# B142A.net
KiCad netlist of a schematic drawn in EAGLE
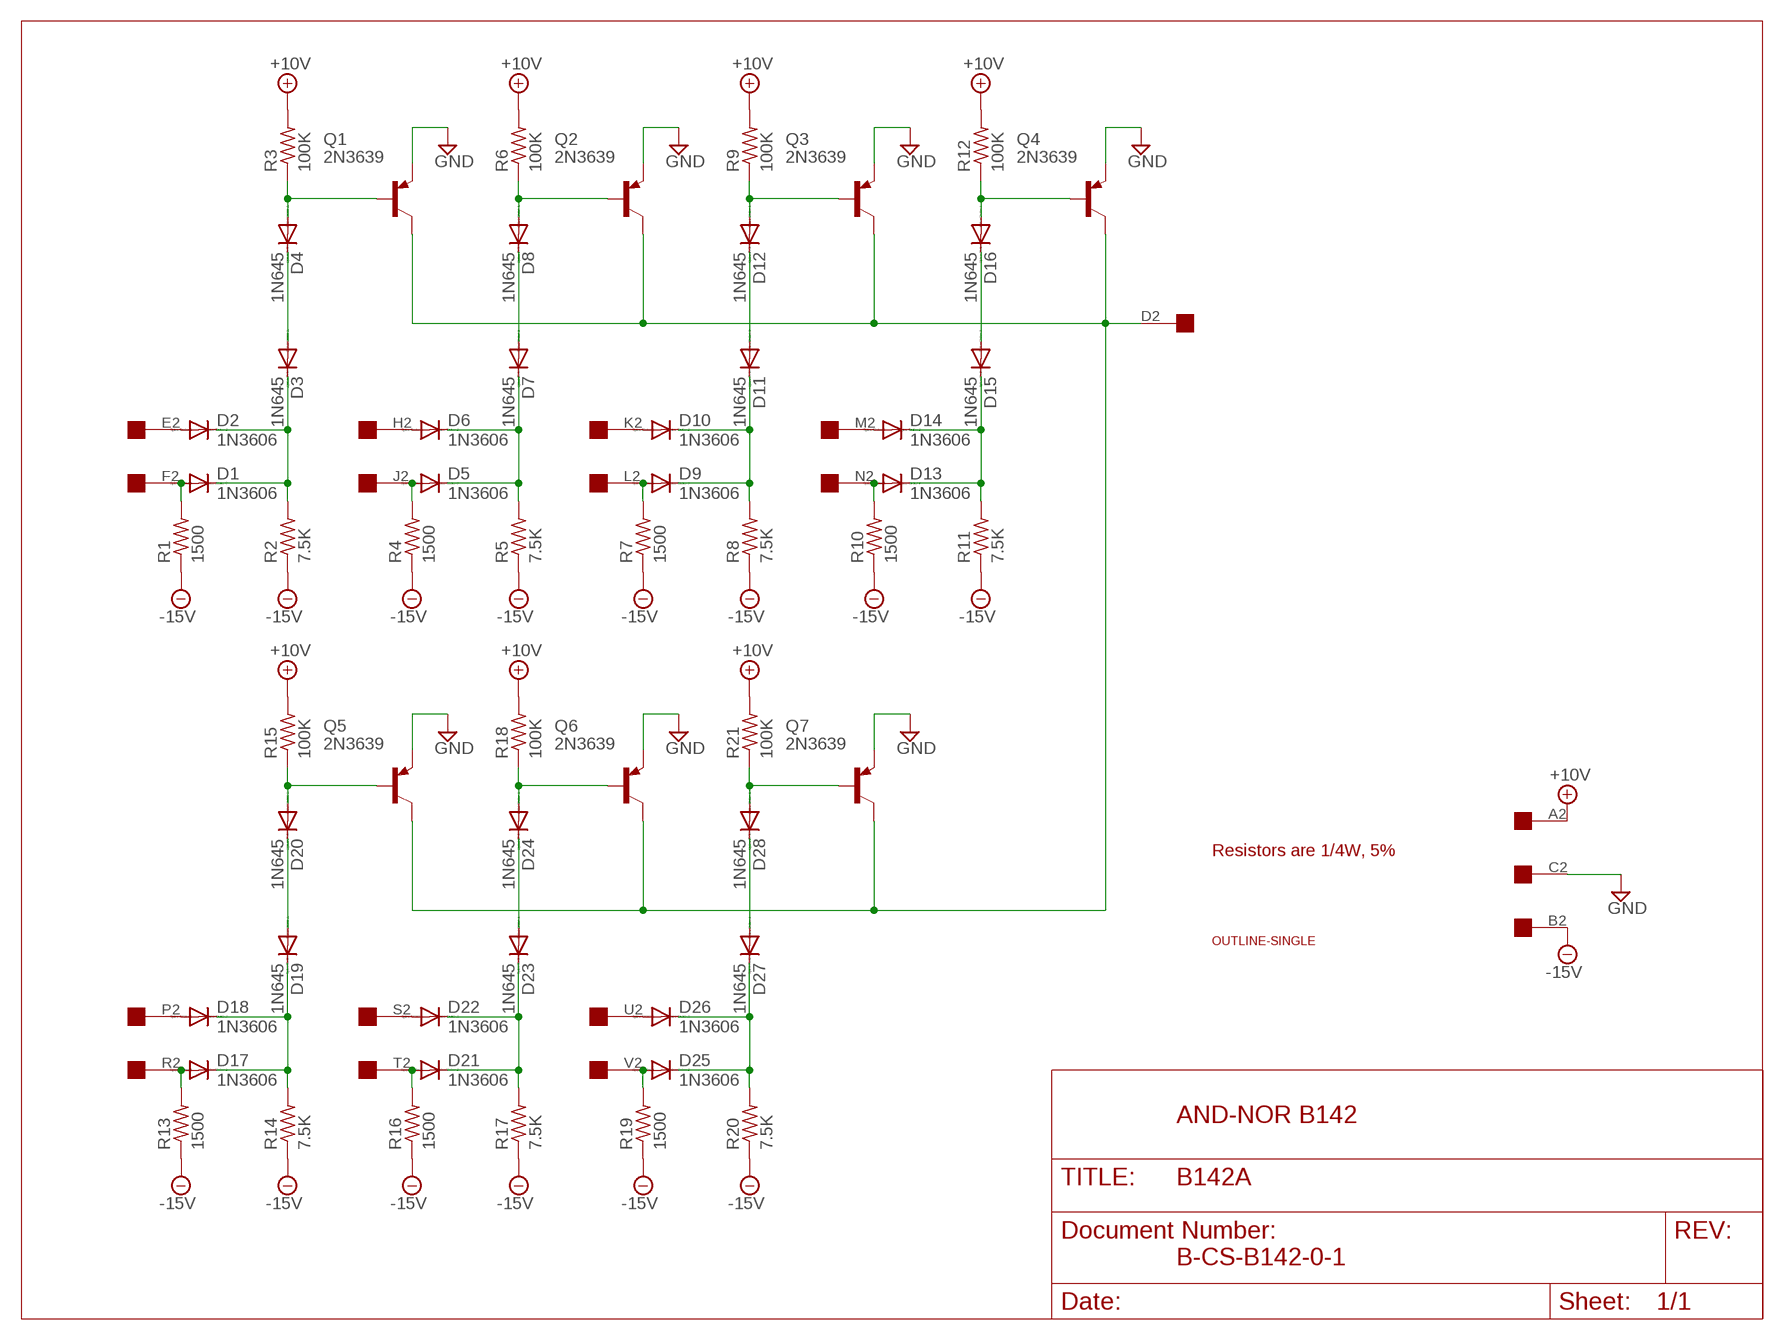
[diagram p0: schematic, sheet 1]

(export (version "E")
  (design (tool "Eeschema 10.0.6"))
  (components
    (comp (ref "D1")
      (value "1N3606")
      (footprint "eagle-import:DO35-10")
      (libsource (lib "eagle-import") (part "1N4148DO35-10"))
    )
    (comp (ref "D2")
      (value "1N3606")
      (footprint "eagle-import:DO35-10")
      (libsource (lib "eagle-import") (part "1N4148DO35-10"))
    )
    (comp (ref "D3")
      (value "1N645")
      (footprint "eagle-import:DO35-10")
      (libsource (lib "eagle-import") (part "1N4148DO35-10"))
    )
    (comp (ref "D4")
      (value "1N645")
      (footprint "eagle-import:DO35-10")
      (libsource (lib "eagle-import") (part "1N4148DO35-10"))
    )
    (comp (ref "D5")
      (value "1N3606")
      (footprint "eagle-import:DO35-10")
      (libsource (lib "eagle-import") (part "1N4148DO35-10"))
    )
    (comp (ref "D6")
      (value "1N3606")
      (footprint "eagle-import:DO35-10")
      (libsource (lib "eagle-import") (part "1N4148DO35-10"))
    )
    (comp (ref "D7")
      (value "1N645")
      (footprint "eagle-import:DO35-10")
      (libsource (lib "eagle-import") (part "1N4148DO35-10"))
    )
    (comp (ref "D8")
      (value "1N645")
      (footprint "eagle-import:DO35-10")
      (libsource (lib "eagle-import") (part "1N4148DO35-10"))
    )
    (comp (ref "D9")
      (value "1N3606")
      (footprint "eagle-import:DO35-10")
      (libsource (lib "eagle-import") (part "1N4148DO35-10"))
    )
    (comp (ref "D10")
      (value "1N3606")
      (footprint "eagle-import:DO35-10")
      (libsource (lib "eagle-import") (part "1N4148DO35-10"))
    )
    (comp (ref "D11")
      (value "1N645")
      (footprint "eagle-import:DO35-10")
      (libsource (lib "eagle-import") (part "1N4148DO35-10"))
    )
    (comp (ref "D12")
      (value "1N645")
      (footprint "eagle-import:DO35-10")
      (libsource (lib "eagle-import") (part "1N4148DO35-10"))
    )
    (comp (ref "D13")
      (value "1N3606")
      (footprint "eagle-import:DO35-10")
      (libsource (lib "eagle-import") (part "1N4148DO35-10"))
    )
    (comp (ref "D14")
      (value "1N3606")
      (footprint "eagle-import:DO35-10")
      (libsource (lib "eagle-import") (part "1N4148DO35-10"))
    )
    (comp (ref "D15")
      (value "1N645")
      (footprint "eagle-import:DO35-10")
      (libsource (lib "eagle-import") (part "1N4148DO35-10"))
    )
    (comp (ref "D16")
      (value "1N645")
      (footprint "eagle-import:DO35-10")
      (libsource (lib "eagle-import") (part "1N4148DO35-10"))
    )
    (comp (ref "D17")
      (value "1N3606")
      (footprint "eagle-import:DO35-10")
      (libsource (lib "eagle-import") (part "1N4148DO35-10"))
    )
    (comp (ref "D18")
      (value "1N3606")
      (footprint "eagle-import:DO35-10")
      (libsource (lib "eagle-import") (part "1N4148DO35-10"))
    )
    (comp (ref "D19")
      (value "1N645")
      (footprint "eagle-import:DO35-10")
      (libsource (lib "eagle-import") (part "1N4148DO35-10"))
    )
    (comp (ref "D20")
      (value "1N645")
      (footprint "eagle-import:DO35-10")
      (libsource (lib "eagle-import") (part "1N4148DO35-10"))
    )
    (comp (ref "D21")
      (value "1N3606")
      (footprint "eagle-import:DO35-10")
      (libsource (lib "eagle-import") (part "1N4148DO35-10"))
    )
    (comp (ref "D22")
      (value "1N3606")
      (footprint "eagle-import:DO35-10")
      (libsource (lib "eagle-import") (part "1N4148DO35-10"))
    )
    (comp (ref "D23")
      (value "1N645")
      (footprint "eagle-import:DO35-10")
      (libsource (lib "eagle-import") (part "1N4148DO35-10"))
    )
    (comp (ref "D24")
      (value "1N645")
      (footprint "eagle-import:DO35-10")
      (libsource (lib "eagle-import") (part "1N4148DO35-10"))
    )
    (comp (ref "D25")
      (value "1N3606")
      (footprint "eagle-import:DO35-10")
      (libsource (lib "eagle-import") (part "1N4148DO35-10"))
    )
    (comp (ref "D26")
      (value "1N3606")
      (footprint "eagle-import:DO35-10")
      (libsource (lib "eagle-import") (part "1N4148DO35-10"))
    )
    (comp (ref "D27")
      (value "1N645")
      (footprint "eagle-import:DO35-10")
      (libsource (lib "eagle-import") (part "1N4148DO35-10"))
    )
    (comp (ref "D28")
      (value "1N645")
      (footprint "eagle-import:DO35-10")
      (libsource (lib "eagle-import") (part "1N4148DO35-10"))
    )
    (comp (ref "Q1")
      (value "2N3639")
      (footprint "eagle-import:TO39")
      (libsource (lib "eagle-import") (part "2N3637"))
    )
    (comp (ref "Q2")
      (value "2N3639")
      (footprint "eagle-import:TO39")
      (libsource (lib "eagle-import") (part "2N3637"))
    )
    (comp (ref "Q3")
      (value "2N3639")
      (footprint "eagle-import:TO39")
      (libsource (lib "eagle-import") (part "2N3637"))
    )
    (comp (ref "Q4")
      (value "2N3639")
      (footprint "eagle-import:TO39")
      (libsource (lib "eagle-import") (part "2N3637"))
    )
    (comp (ref "Q5")
      (value "2N3639")
      (footprint "eagle-import:TO39")
      (libsource (lib "eagle-import") (part "2N3637"))
    )
    (comp (ref "Q6")
      (value "2N3639")
      (footprint "eagle-import:TO39")
      (libsource (lib "eagle-import") (part "2N3637"))
    )
    (comp (ref "Q7")
      (value "2N3639")
      (footprint "eagle-import:TO39")
      (libsource (lib "eagle-import") (part "2N3637"))
    )
    (comp (ref "R1")
      (value "1500")
      (footprint "eagle-import:0207_10")
      (libsource (lib "eagle-import") (part "R-US_0207/10"))
    )
    (comp (ref "R2")
      (value "7.5K")
      (footprint "eagle-import:0207_10")
      (libsource (lib "eagle-import") (part "R-US_0207/10"))
    )
    (comp (ref "R3")
      (value "100K")
      (footprint "eagle-import:0207_10")
      (libsource (lib "eagle-import") (part "R-US_0207/10"))
    )
    (comp (ref "R4")
      (value "1500")
      (footprint "eagle-import:0207_10")
      (libsource (lib "eagle-import") (part "R-US_0207/10"))
    )
    (comp (ref "R5")
      (value "7.5K")
      (footprint "eagle-import:0207_10")
      (libsource (lib "eagle-import") (part "R-US_0207/10"))
    )
    (comp (ref "R6")
      (value "100K")
      (footprint "eagle-import:0207_10")
      (libsource (lib "eagle-import") (part "R-US_0207/10"))
    )
    (comp (ref "R7")
      (value "1500")
      (footprint "eagle-import:0207_10")
      (libsource (lib "eagle-import") (part "R-US_0207/10"))
    )
    (comp (ref "R8")
      (value "7.5K")
      (footprint "eagle-import:0207_10")
      (libsource (lib "eagle-import") (part "R-US_0207/10"))
    )
    (comp (ref "R9")
      (value "100K")
      (footprint "eagle-import:0207_10")
      (libsource (lib "eagle-import") (part "R-US_0207/10"))
    )
    (comp (ref "R10")
      (value "1500")
      (footprint "eagle-import:0207_10")
      (libsource (lib "eagle-import") (part "R-US_0207/10"))
    )
    (comp (ref "R11")
      (value "7.5K")
      (footprint "eagle-import:0207_10")
      (libsource (lib "eagle-import") (part "R-US_0207/10"))
    )
    (comp (ref "R12")
      (value "100K")
      (footprint "eagle-import:0207_10")
      (libsource (lib "eagle-import") (part "R-US_0207/10"))
    )
    (comp (ref "R13")
      (value "1500")
      (footprint "eagle-import:0207_10")
      (libsource (lib "eagle-import") (part "R-US_0207/10"))
    )
    (comp (ref "R14")
      (value "7.5K")
      (footprint "eagle-import:0207_10")
      (libsource (lib "eagle-import") (part "R-US_0207/10"))
    )
    (comp (ref "R15")
      (value "100K")
      (footprint "eagle-import:0207_10")
      (libsource (lib "eagle-import") (part "R-US_0207/10"))
    )
    (comp (ref "R16")
      (value "1500")
      (footprint "eagle-import:0207_10")
      (libsource (lib "eagle-import") (part "R-US_0207/10"))
    )
    (comp (ref "R17")
      (value "7.5K")
      (footprint "eagle-import:0207_10")
      (libsource (lib "eagle-import") (part "R-US_0207/10"))
    )
    (comp (ref "R18")
      (value "100K")
      (footprint "eagle-import:0207_10")
      (libsource (lib "eagle-import") (part "R-US_0207/10"))
    )
    (comp (ref "R19")
      (value "1500")
      (footprint "eagle-import:0207_10")
      (libsource (lib "eagle-import") (part "R-US_0207/10"))
    )
    (comp (ref "R20")
      (value "7.5K")
      (footprint "eagle-import:0207_10")
      (libsource (lib "eagle-import") (part "R-US_0207/10"))
    )
    (comp (ref "R21")
      (value "100K")
      (footprint "eagle-import:0207_10")
      (libsource (lib "eagle-import") (part "R-US_0207/10"))
    )
    (comp (ref "U$1")
      (value "OUTLINE-SINGLE")
      (footprint "eagle-import:SINGLE")
      (libsource (lib "eagle-import") (part "OUTLINE-SINGLE"))
    )
    (comp (ref "U$2")
      (value "EDGE-1")
      (footprint "eagle-import:EDGE-CON1")
      (libsource (lib "eagle-import") (part "EDGE-1"))
    )
  )
  (nets
    (net (code "1") (name "+10V") (class "Default")
      (node (ref "R12") (pin "2") (pinfunction "2_2") (pintype "passive"))
      (node (ref "R15") (pin "2") (pinfunction "2_2") (pintype "passive"))
      (node (ref "R18") (pin "2") (pinfunction "2_2") (pintype "passive"))
      (node (ref "R21") (pin "2") (pinfunction "2_2") (pintype "passive"))
      (node (ref "R3") (pin "2") (pinfunction "2_2") (pintype "passive"))
      (node (ref "R6") (pin "2") (pinfunction "2_2") (pintype "passive"))
      (node (ref "R9") (pin "2") (pinfunction "2_2") (pintype "passive"))
      (node (ref "U$2") (pin "A2") (pinfunction "1_A2") (pintype "bidirectional"))
    )
    (net (code "2") (name "-15V") (class "Default")
      (node (ref "R1") (pin "1") (pinfunction "1_1") (pintype "passive"))
      (node (ref "R10") (pin "1") (pinfunction "1_1") (pintype "passive"))
      (node (ref "R11") (pin "1") (pinfunction "1_1") (pintype "passive"))
      (node (ref "R13") (pin "1") (pinfunction "1_1") (pintype "passive"))
      (node (ref "R14") (pin "1") (pinfunction "1_1") (pintype "passive"))
      (node (ref "R16") (pin "1") (pinfunction "1_1") (pintype "passive"))
      (node (ref "R17") (pin "1") (pinfunction "1_1") (pintype "passive"))
      (node (ref "R19") (pin "1") (pinfunction "1_1") (pintype "passive"))
      (node (ref "R2") (pin "1") (pinfunction "1_1") (pintype "passive"))
      (node (ref "R20") (pin "1") (pinfunction "1_1") (pintype "passive"))
      (node (ref "R4") (pin "1") (pinfunction "1_1") (pintype "passive"))
      (node (ref "R5") (pin "1") (pinfunction "1_1") (pintype "passive"))
      (node (ref "R7") (pin "1") (pinfunction "1_1") (pintype "passive"))
      (node (ref "R8") (pin "1") (pinfunction "1_1") (pintype "passive"))
      (node (ref "U$2") (pin "B2") (pinfunction "1_B2") (pintype "bidirectional"))
    )
    (net (code "3") (name "GND") (class "Default")
      (node (ref "Q1") (pin "1") (pinfunction "E_1") (pintype "passive"))
      (node (ref "Q2") (pin "1") (pinfunction "E_1") (pintype "passive"))
      (node (ref "Q3") (pin "1") (pinfunction "E_1") (pintype "passive"))
      (node (ref "Q4") (pin "1") (pinfunction "E_1") (pintype "passive"))
      (node (ref "Q5") (pin "1") (pinfunction "E_1") (pintype "passive"))
      (node (ref "Q6") (pin "1") (pinfunction "E_1") (pintype "passive"))
      (node (ref "Q7") (pin "1") (pinfunction "E_1") (pintype "passive"))
      (node (ref "U$2") (pin "C2") (pinfunction "1_C2") (pintype "bidirectional"))
    )
    (net (code "4") (name "Net-(D1-PadC)") (class "Default")
      (node (ref "D1") (pin "C") (pinfunction "C_C") (pintype "passive"))
      (node (ref "D2") (pin "C") (pinfunction "C_C") (pintype "passive"))
      (node (ref "D3") (pin "C") (pinfunction "C_C") (pintype "passive"))
      (node (ref "R2") (pin "2") (pinfunction "2_2") (pintype "passive"))
    )
    (net (code "5") (name "Net-(D3-PadA)") (class "Default")
      (node (ref "D3") (pin "A") (pinfunction "A_A") (pintype "passive"))
      (node (ref "D4") (pin "C") (pinfunction "C_C") (pintype "passive"))
    )
    (net (code "6") (name "Net-(D5-PadC)") (class "Default")
      (node (ref "D5") (pin "C") (pinfunction "C_C") (pintype "passive"))
      (node (ref "D6") (pin "C") (pinfunction "C_C") (pintype "passive"))
      (node (ref "D7") (pin "C") (pinfunction "C_C") (pintype "passive"))
      (node (ref "R5") (pin "2") (pinfunction "2_2") (pintype "passive"))
    )
    (net (code "7") (name "Net-(D7-PadA)") (class "Default")
      (node (ref "D7") (pin "A") (pinfunction "A_A") (pintype "passive"))
      (node (ref "D8") (pin "C") (pinfunction "C_C") (pintype "passive"))
    )
    (net (code "8") (name "Net-(D10-PadC)") (class "Default")
      (node (ref "D10") (pin "C") (pinfunction "C_C") (pintype "passive"))
      (node (ref "D11") (pin "C") (pinfunction "C_C") (pintype "passive"))
      (node (ref "D9") (pin "C") (pinfunction "C_C") (pintype "passive"))
      (node (ref "R8") (pin "2") (pinfunction "2_2") (pintype "passive"))
    )
    (net (code "9") (name "Net-(D11-PadA)") (class "Default")
      (node (ref "D11") (pin "A") (pinfunction "A_A") (pintype "passive"))
      (node (ref "D12") (pin "C") (pinfunction "C_C") (pintype "passive"))
    )
    (net (code "10") (name "Net-(D13-PadC)") (class "Default")
      (node (ref "D13") (pin "C") (pinfunction "C_C") (pintype "passive"))
      (node (ref "D14") (pin "C") (pinfunction "C_C") (pintype "passive"))
      (node (ref "D15") (pin "C") (pinfunction "C_C") (pintype "passive"))
      (node (ref "R11") (pin "2") (pinfunction "2_2") (pintype "passive"))
    )
    (net (code "11") (name "Net-(D15-PadA)") (class "Default")
      (node (ref "D15") (pin "A") (pinfunction "A_A") (pintype "passive"))
      (node (ref "D16") (pin "C") (pinfunction "C_C") (pintype "passive"))
    )
    (net (code "12") (name "Net-(D17-PadC)") (class "Default")
      (node (ref "D17") (pin "C") (pinfunction "C_C") (pintype "passive"))
      (node (ref "D18") (pin "C") (pinfunction "C_C") (pintype "passive"))
      (node (ref "D19") (pin "C") (pinfunction "C_C") (pintype "passive"))
      (node (ref "R14") (pin "2") (pinfunction "2_2") (pintype "passive"))
    )
    (net (code "13") (name "Net-(D19-PadA)") (class "Default")
      (node (ref "D19") (pin "A") (pinfunction "A_A") (pintype "passive"))
      (node (ref "D20") (pin "C") (pinfunction "C_C") (pintype "passive"))
    )
    (net (code "14") (name "Net-(D21-PadC)") (class "Default")
      (node (ref "D21") (pin "C") (pinfunction "C_C") (pintype "passive"))
      (node (ref "D22") (pin "C") (pinfunction "C_C") (pintype "passive"))
      (node (ref "D23") (pin "C") (pinfunction "C_C") (pintype "passive"))
      (node (ref "R17") (pin "2") (pinfunction "2_2") (pintype "passive"))
    )
    (net (code "15") (name "Net-(D23-PadA)") (class "Default")
      (node (ref "D23") (pin "A") (pinfunction "A_A") (pintype "passive"))
      (node (ref "D24") (pin "C") (pinfunction "C_C") (pintype "passive"))
    )
    (net (code "16") (name "Net-(D25-PadC)") (class "Default")
      (node (ref "D25") (pin "C") (pinfunction "C_C") (pintype "passive"))
      (node (ref "D26") (pin "C") (pinfunction "C_C") (pintype "passive"))
      (node (ref "D27") (pin "C") (pinfunction "C_C") (pintype "passive"))
      (node (ref "R20") (pin "2") (pinfunction "2_2") (pintype "passive"))
    )
    (net (code "17") (name "Net-(D27-PadA)") (class "Default")
      (node (ref "D27") (pin "A") (pinfunction "A_A") (pintype "passive"))
      (node (ref "D28") (pin "C") (pinfunction "C_C") (pintype "passive"))
    )
    (net (code "18") (name "Net-(Q1-B)") (class "Default")
      (node (ref "D4") (pin "A") (pinfunction "A_A") (pintype "passive"))
      (node (ref "Q1") (pin "2") (pinfunction "B_2") (pintype "passive"))
      (node (ref "R3") (pin "1") (pinfunction "1_1") (pintype "passive"))
    )
    (net (code "19") (name "Net-(Q1-C)") (class "Default")
      (node (ref "Q1") (pin "3") (pinfunction "C_3") (pintype "passive"))
      (node (ref "Q2") (pin "3") (pinfunction "C_3") (pintype "passive"))
      (node (ref "Q3") (pin "3") (pinfunction "C_3") (pintype "passive"))
      (node (ref "Q4") (pin "3") (pinfunction "C_3") (pintype "passive"))
      (node (ref "Q5") (pin "3") (pinfunction "C_3") (pintype "passive"))
      (node (ref "Q6") (pin "3") (pinfunction "C_3") (pintype "passive"))
      (node (ref "Q7") (pin "3") (pinfunction "C_3") (pintype "passive"))
      (node (ref "U$2") (pin "D2") (pinfunction "1_D2") (pintype "bidirectional"))
    )
    (net (code "20") (name "Net-(Q2-B)") (class "Default")
      (node (ref "D8") (pin "A") (pinfunction "A_A") (pintype "passive"))
      (node (ref "Q2") (pin "2") (pinfunction "B_2") (pintype "passive"))
      (node (ref "R6") (pin "1") (pinfunction "1_1") (pintype "passive"))
    )
    (net (code "21") (name "Net-(Q3-B)") (class "Default")
      (node (ref "D12") (pin "A") (pinfunction "A_A") (pintype "passive"))
      (node (ref "Q3") (pin "2") (pinfunction "B_2") (pintype "passive"))
      (node (ref "R9") (pin "1") (pinfunction "1_1") (pintype "passive"))
    )
    (net (code "22") (name "Net-(Q4-B)") (class "Default")
      (node (ref "D16") (pin "A") (pinfunction "A_A") (pintype "passive"))
      (node (ref "Q4") (pin "2") (pinfunction "B_2") (pintype "passive"))
      (node (ref "R12") (pin "1") (pinfunction "1_1") (pintype "passive"))
    )
    (net (code "23") (name "Net-(Q5-B)") (class "Default")
      (node (ref "D20") (pin "A") (pinfunction "A_A") (pintype "passive"))
      (node (ref "Q5") (pin "2") (pinfunction "B_2") (pintype "passive"))
      (node (ref "R15") (pin "1") (pinfunction "1_1") (pintype "passive"))
    )
    (net (code "24") (name "Net-(Q6-B)") (class "Default")
      (node (ref "D24") (pin "A") (pinfunction "A_A") (pintype "passive"))
      (node (ref "Q6") (pin "2") (pinfunction "B_2") (pintype "passive"))
      (node (ref "R18") (pin "1") (pinfunction "1_1") (pintype "passive"))
    )
    (net (code "25") (name "Net-(Q7-B)") (class "Default")
      (node (ref "D28") (pin "A") (pinfunction "A_A") (pintype "passive"))
      (node (ref "Q7") (pin "2") (pinfunction "B_2") (pintype "passive"))
      (node (ref "R21") (pin "1") (pinfunction "1_1") (pintype "passive"))
    )
    (net (code "26") (name "Net-(U$2E-1)") (class "Default")
      (node (ref "D2") (pin "A") (pinfunction "A_A") (pintype "passive"))
      (node (ref "U$2") (pin "E2") (pinfunction "1_E2") (pintype "bidirectional"))
    )
    (net (code "27") (name "Net-(U$2F-1)") (class "Default")
      (node (ref "D1") (pin "A") (pinfunction "A_A") (pintype "passive"))
      (node (ref "R1") (pin "2") (pinfunction "2_2") (pintype "passive"))
      (node (ref "U$2") (pin "F2") (pinfunction "1_F2") (pintype "bidirectional"))
    )
    (net (code "28") (name "Net-(U$2G-1)") (class "Default")
      (node (ref "D6") (pin "A") (pinfunction "A_A") (pintype "passive"))
      (node (ref "U$2") (pin "H2") (pinfunction "1_H2") (pintype "bidirectional"))
    )
    (net (code "29") (name "Net-(U$2H-1)") (class "Default")
      (node (ref "D5") (pin "A") (pinfunction "A_A") (pintype "passive"))
      (node (ref "R4") (pin "2") (pinfunction "2_2") (pintype "passive"))
      (node (ref "U$2") (pin "J2") (pinfunction "1_J2") (pintype "bidirectional"))
    )
    (net (code "30") (name "Net-(U$2I-1)") (class "Default")
      (node (ref "D10") (pin "A") (pinfunction "A_A") (pintype "passive"))
      (node (ref "U$2") (pin "K2") (pinfunction "1_K2") (pintype "bidirectional"))
    )
    (net (code "31") (name "Net-(U$2J-1)") (class "Default")
      (node (ref "D9") (pin "A") (pinfunction "A_A") (pintype "passive"))
      (node (ref "R7") (pin "2") (pinfunction "2_2") (pintype "passive"))
      (node (ref "U$2") (pin "L2") (pinfunction "1_L2") (pintype "bidirectional"))
    )
    (net (code "32") (name "Net-(U$2K-1)") (class "Default")
      (node (ref "D14") (pin "A") (pinfunction "A_A") (pintype "passive"))
      (node (ref "U$2") (pin "M2") (pinfunction "1_M2") (pintype "bidirectional"))
    )
    (net (code "33") (name "Net-(U$2L-1)") (class "Default")
      (node (ref "D13") (pin "A") (pinfunction "A_A") (pintype "passive"))
      (node (ref "R10") (pin "2") (pinfunction "2_2") (pintype "passive"))
      (node (ref "U$2") (pin "N2") (pinfunction "1_N2") (pintype "bidirectional"))
    )
    (net (code "34") (name "Net-(U$2M-1)") (class "Default")
      (node (ref "D18") (pin "A") (pinfunction "A_A") (pintype "passive"))
      (node (ref "U$2") (pin "P2") (pinfunction "1_P2") (pintype "bidirectional"))
    )
    (net (code "35") (name "Net-(U$2N-1)") (class "Default")
      (node (ref "D17") (pin "A") (pinfunction "A_A") (pintype "passive"))
      (node (ref "R13") (pin "2") (pinfunction "2_2") (pintype "passive"))
      (node (ref "U$2") (pin "R2") (pinfunction "1_R2") (pintype "bidirectional"))
    )
    (net (code "36") (name "Net-(U$2O-1)") (class "Default")
      (node (ref "D22") (pin "A") (pinfunction "A_A") (pintype "passive"))
      (node (ref "U$2") (pin "S2") (pinfunction "1_S2") (pintype "bidirectional"))
    )
    (net (code "37") (name "Net-(U$2P-1)") (class "Default")
      (node (ref "D21") (pin "A") (pinfunction "A_A") (pintype "passive"))
      (node (ref "R16") (pin "2") (pinfunction "2_2") (pintype "passive"))
      (node (ref "U$2") (pin "T2") (pinfunction "1_T2") (pintype "bidirectional"))
    )
    (net (code "38") (name "Net-(U$2Q-1)") (class "Default")
      (node (ref "D26") (pin "A") (pinfunction "A_A") (pintype "passive"))
      (node (ref "U$2") (pin "U2") (pinfunction "1_U2") (pintype "bidirectional"))
    )
    (net (code "39") (name "Net-(U$2R-1)") (class "Default")
      (node (ref "D25") (pin "A") (pinfunction "A_A") (pintype "passive"))
      (node (ref "R19") (pin "2") (pinfunction "2_2") (pintype "passive"))
      (node (ref "U$2") (pin "V2") (pinfunction "1_V2") (pintype "bidirectional"))
    )
  )
)
